# GPR.net
KiCad netlist of a schematic drawn in EAGLE
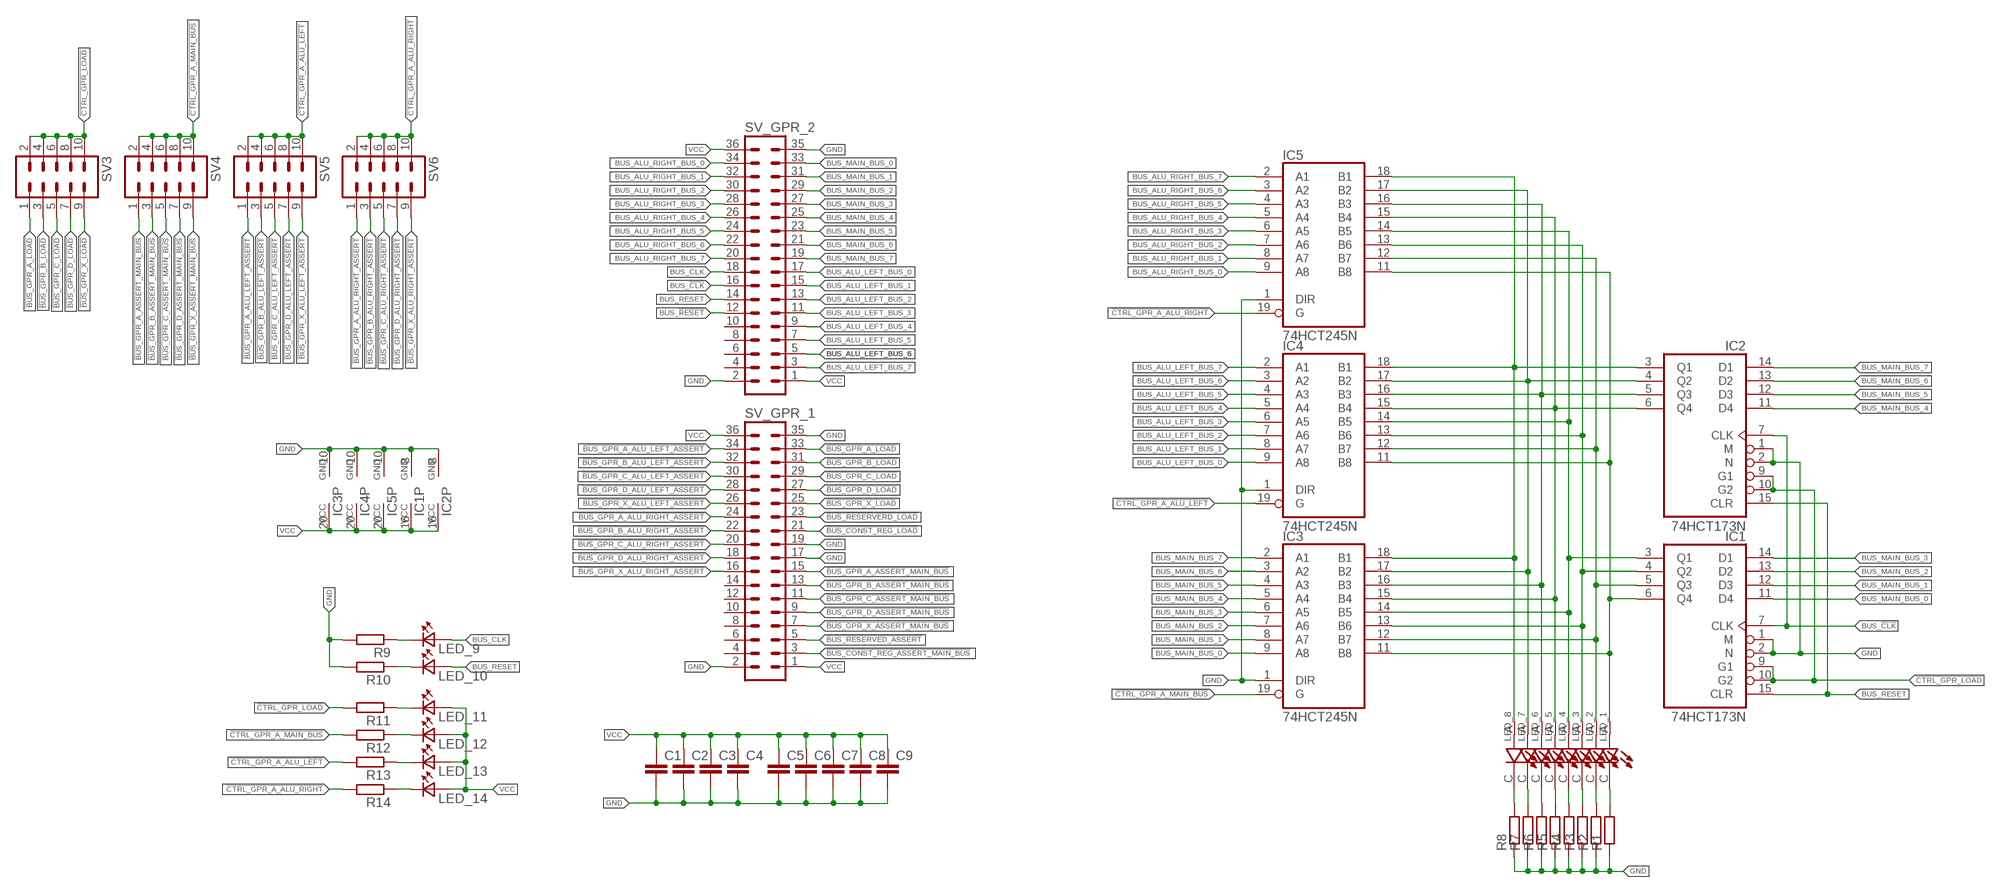
[diagram p0: schematic, sheet 1]

(export (version "E")
  (design (tool "Eeschema 10.0.6"))
  (components
    (comp (ref "C1")
      (value "C-EUC0805")
      (footprint "eagle-import:C0805")
      (libsource (lib "eagle-import") (part "C-EUC0805"))
    )
    (comp (ref "C2")
      (value "C-EUC0805")
      (footprint "eagle-import:C0805")
      (libsource (lib "eagle-import") (part "C-EUC0805"))
    )
    (comp (ref "C3")
      (value "C-EUC0805")
      (footprint "eagle-import:C0805")
      (libsource (lib "eagle-import") (part "C-EUC0805"))
    )
    (comp (ref "C4")
      (value "C-EUC0805")
      (footprint "eagle-import:C0805")
      (libsource (lib "eagle-import") (part "C-EUC0805"))
    )
    (comp (ref "C5")
      (value "C-EUC0805")
      (footprint "eagle-import:C0805")
      (libsource (lib "eagle-import") (part "C-EUC0805"))
    )
    (comp (ref "C6")
      (value "C-EUC0805")
      (footprint "eagle-import:C0805")
      (libsource (lib "eagle-import") (part "C-EUC0805"))
    )
    (comp (ref "C7")
      (value "C-EUC0805")
      (footprint "eagle-import:C0805")
      (libsource (lib "eagle-import") (part "C-EUC0805"))
    )
    (comp (ref "C8")
      (value "C-EUC0805")
      (footprint "eagle-import:C0805")
      (libsource (lib "eagle-import") (part "C-EUC0805"))
    )
    (comp (ref "C9")
      (value "C-EUC0805")
      (footprint "eagle-import:C0805")
      (libsource (lib "eagle-import") (part "C-EUC0805"))
    )
    (comp (ref "IC1")
      (value "74HCT173N")
      (footprint "eagle-import:DIL16")
      (libsource (lib "eagle-import") (part "74173NHCT"))
    )
    (comp (ref "IC2")
      (value "74HCT173N")
      (footprint "eagle-import:DIL16")
      (libsource (lib "eagle-import") (part "74173NHCT"))
    )
    (comp (ref "IC3")
      (value "74HCT245N")
      (footprint "eagle-import:DIL20")
      (libsource (lib "eagle-import") (part "74245NHCT"))
    )
    (comp (ref "IC4")
      (value "74HCT245N")
      (footprint "eagle-import:DIL20")
      (libsource (lib "eagle-import") (part "74245NHCT"))
    )
    (comp (ref "IC5")
      (value "74HCT245N")
      (footprint "eagle-import:DIL20")
      (libsource (lib "eagle-import") (part "74245NHCT"))
    )
    (comp (ref "LED_1")
      (value "LTST-C193KRKT-5A")
      (footprint "eagle-import:LEDC1608X45N")
      (fields (field (name "MANUFACTURER") "Lite-On"))
      (libsource (lib "eagle-import") (part "LTST-C193KRKT-5A"))
    )
    (comp (ref "LED_2")
      (value "LTST-C193KRKT-5A")
      (footprint "eagle-import:LEDC1608X45N")
      (fields (field (name "MANUFACTURER") "Lite-On"))
      (libsource (lib "eagle-import") (part "LTST-C193KRKT-5A"))
    )
    (comp (ref "LED_3")
      (value "LTST-C193KRKT-5A")
      (footprint "eagle-import:LEDC1608X45N")
      (fields (field (name "MANUFACTURER") "Lite-On"))
      (libsource (lib "eagle-import") (part "LTST-C193KRKT-5A"))
    )
    (comp (ref "LED_4")
      (value "LTST-C193KRKT-5A")
      (footprint "eagle-import:LEDC1608X45N")
      (fields (field (name "MANUFACTURER") "Lite-On"))
      (libsource (lib "eagle-import") (part "LTST-C193KRKT-5A"))
    )
    (comp (ref "LED_5")
      (value "LTST-C193KRKT-5A")
      (footprint "eagle-import:LEDC1608X45N")
      (fields (field (name "MANUFACTURER") "Lite-On"))
      (libsource (lib "eagle-import") (part "LTST-C193KRKT-5A"))
    )
    (comp (ref "LED_6")
      (value "LTST-C193KRKT-5A")
      (footprint "eagle-import:LEDC1608X45N")
      (fields (field (name "MANUFACTURER") "Lite-On"))
      (libsource (lib "eagle-import") (part "LTST-C193KRKT-5A"))
    )
    (comp (ref "LED_7")
      (value "LTST-C193KRKT-5A")
      (footprint "eagle-import:LEDC1608X45N")
      (fields (field (name "MANUFACTURER") "Lite-On"))
      (libsource (lib "eagle-import") (part "LTST-C193KRKT-5A"))
    )
    (comp (ref "LED_8")
      (value "LTST-C193KRKT-5A")
      (footprint "eagle-import:LEDC1608X45N")
      (fields (field (name "MANUFACTURER") "Lite-On"))
      (libsource (lib "eagle-import") (part "LTST-C193KRKT-5A"))
    )
    (comp (ref "LED_9")
      (value "LTST-C193TBKT-5A")
      (footprint "eagle-import:0603")
      (libsource (lib "eagle-import") (part "LTST-C193TBKT-5A"))
    )
    (comp (ref "LED_10")
      (value "LTST-C193TBKT-5A")
      (footprint "eagle-import:0603")
      (libsource (lib "eagle-import") (part "LTST-C193TBKT-5A"))
    )
    (comp (ref "LED_11")
      (value "LTST-C193TBKT-5A")
      (footprint "eagle-import:0603")
      (libsource (lib "eagle-import") (part "LTST-C193TBKT-5A"))
    )
    (comp (ref "LED_12")
      (value "LTST-C193TBKT-5A")
      (footprint "eagle-import:0603")
      (libsource (lib "eagle-import") (part "LTST-C193TBKT-5A"))
    )
    (comp (ref "LED_13")
      (value "LTST-C193TBKT-5A")
      (footprint "eagle-import:0603")
      (libsource (lib "eagle-import") (part "LTST-C193TBKT-5A"))
    )
    (comp (ref "LED_14")
      (value "LTST-C193TBKT-5A")
      (footprint "eagle-import:0603")
      (libsource (lib "eagle-import") (part "LTST-C193TBKT-5A"))
    )
    (comp (ref "R1")
      (value "R-EU_R0805")
      (footprint "eagle-import:R0805")
      (libsource (lib "eagle-import") (part "R-EU_R0805"))
    )
    (comp (ref "R2")
      (value "R-EU_R0805")
      (footprint "eagle-import:R0805")
      (libsource (lib "eagle-import") (part "R-EU_R0805"))
    )
    (comp (ref "R3")
      (value "R-EU_R0805")
      (footprint "eagle-import:R0805")
      (libsource (lib "eagle-import") (part "R-EU_R0805"))
    )
    (comp (ref "R4")
      (value "R-EU_R0805")
      (footprint "eagle-import:R0805")
      (libsource (lib "eagle-import") (part "R-EU_R0805"))
    )
    (comp (ref "R5")
      (value "R-EU_R0805")
      (footprint "eagle-import:R0805")
      (libsource (lib "eagle-import") (part "R-EU_R0805"))
    )
    (comp (ref "R6")
      (value "R-EU_R0805")
      (footprint "eagle-import:R0805")
      (libsource (lib "eagle-import") (part "R-EU_R0805"))
    )
    (comp (ref "R7")
      (value "R-EU_R0805")
      (footprint "eagle-import:R0805")
      (libsource (lib "eagle-import") (part "R-EU_R0805"))
    )
    (comp (ref "R8")
      (value "R-EU_R0805")
      (footprint "eagle-import:R0805")
      (libsource (lib "eagle-import") (part "R-EU_R0805"))
    )
    (comp (ref "R9")
      (value "R-EU_R0805")
      (footprint "eagle-import:R0805")
      (libsource (lib "eagle-import") (part "R-EU_R0805"))
    )
    (comp (ref "R10")
      (value "R-EU_R0805")
      (footprint "eagle-import:R0805")
      (libsource (lib "eagle-import") (part "R-EU_R0805"))
    )
    (comp (ref "R11")
      (value "R-EU_R0805")
      (footprint "eagle-import:R0805")
      (libsource (lib "eagle-import") (part "R-EU_R0805"))
    )
    (comp (ref "R12")
      (value "R-EU_R0805")
      (footprint "eagle-import:R0805")
      (libsource (lib "eagle-import") (part "R-EU_R0805"))
    )
    (comp (ref "R13")
      (value "R-EU_R0805")
      (footprint "eagle-import:R0805")
      (libsource (lib "eagle-import") (part "R-EU_R0805"))
    )
    (comp (ref "R14")
      (value "R-EU_R0805")
      (footprint "eagle-import:R0805")
      (libsource (lib "eagle-import") (part "R-EU_R0805"))
    )
    (comp (ref "SV3")
      (value "MA05-2")
      (footprint "eagle-import:MA05-2")
      (libsource (lib "eagle-import") (part "MA05-2"))
    )
    (comp (ref "SV4")
      (value "MA05-2")
      (footprint "eagle-import:MA05-2")
      (libsource (lib "eagle-import") (part "MA05-2"))
    )
    (comp (ref "SV5")
      (value "MA05-2")
      (footprint "eagle-import:MA05-2")
      (libsource (lib "eagle-import") (part "MA05-2"))
    )
    (comp (ref "SV6")
      (value "MA05-2")
      (footprint "eagle-import:MA05-2")
      (libsource (lib "eagle-import") (part "MA05-2"))
    )
    (comp (ref "SV_GPR_1")
      (value "MA18-2")
      (footprint "eagle-import:MA18-2")
      (libsource (lib "eagle-import") (part "MA18-2"))
    )
    (comp (ref "SV_GPR_2")
      (value "MA18-2")
      (footprint "eagle-import:MA18-2")
      (libsource (lib "eagle-import") (part "MA18-2"))
    )
  )
  (nets
    (net (code "1") (name "/BUS_~{CLK}") (class "Default")
      (node (ref "IC1") (pin "7") (pinfunction "CLK_7") (pintype "input"))
      (node (ref "IC2") (pin "7") (pinfunction "CLK_7") (pintype "input"))
      (node (ref "SV_GPR_2") (pin "16") (pinfunction "16_16") (pintype "passive"))
    )
    (net (code "2") (name "/BUS_~{RESET}") (class "Default")
      (node (ref "SV_GPR_2") (pin "12") (pinfunction "12_12") (pintype "passive"))
    )
    (net (code "3") (name "/~{BUS_CONST_REG_ASSERT_MAIN_BUS}") (class "Default")
      (node (ref "SV_GPR_1") (pin "3") (pinfunction "3_3") (pintype "passive"))
    )
    (net (code "4") (name "/~{BUS_CONST_REG_LOAD}") (class "Default")
      (node (ref "SV_GPR_1") (pin "21") (pinfunction "21_21") (pintype "passive"))
    )
    (net (code "5") (name "/~{BUS_GPR_A_ALU_LEFT_ASSERT}") (class "Default")
      (node (ref "SV5") (pin "1") (pinfunction "1_1") (pintype "passive"))
      (node (ref "SV_GPR_1") (pin "34") (pinfunction "34_34") (pintype "passive"))
    )
    (net (code "6") (name "/~{BUS_GPR_A_ALU_RIGHT_ASSERT}") (class "Default")
      (node (ref "SV6") (pin "1") (pinfunction "1_1") (pintype "passive"))
      (node (ref "SV_GPR_1") (pin "24") (pinfunction "24_24") (pintype "passive"))
    )
    (net (code "7") (name "/~{BUS_GPR_A_ASSERT_MAIN_BUS}") (class "Default")
      (node (ref "SV4") (pin "1") (pinfunction "1_1") (pintype "passive"))
      (node (ref "SV_GPR_1") (pin "15") (pinfunction "15_15") (pintype "passive"))
    )
    (net (code "8") (name "/~{BUS_GPR_A_LOAD}") (class "Default")
      (node (ref "SV3") (pin "1") (pinfunction "1_1") (pintype "passive"))
      (node (ref "SV_GPR_1") (pin "33") (pinfunction "33_33") (pintype "passive"))
    )
    (net (code "9") (name "/~{BUS_GPR_B_ALU_LEFT_ASSERT}") (class "Default")
      (node (ref "SV5") (pin "3") (pinfunction "3_3") (pintype "passive"))
      (node (ref "SV_GPR_1") (pin "32") (pinfunction "32_32") (pintype "passive"))
    )
    (net (code "10") (name "/~{BUS_GPR_B_ALU_RIGHT_ASSERT}") (class "Default")
      (node (ref "SV6") (pin "3") (pinfunction "3_3") (pintype "passive"))
      (node (ref "SV_GPR_1") (pin "22") (pinfunction "22_22") (pintype "passive"))
    )
    (net (code "11") (name "/~{BUS_GPR_B_ASSERT_MAIN_BUS}") (class "Default")
      (node (ref "SV4") (pin "3") (pinfunction "3_3") (pintype "passive"))
      (node (ref "SV_GPR_1") (pin "13") (pinfunction "13_13") (pintype "passive"))
    )
    (net (code "12") (name "/~{BUS_GPR_B_LOAD}") (class "Default")
      (node (ref "SV3") (pin "3") (pinfunction "3_3") (pintype "passive"))
      (node (ref "SV_GPR_1") (pin "31") (pinfunction "31_31") (pintype "passive"))
    )
    (net (code "13") (name "/~{BUS_GPR_C_ALU_LEFT_ASSERT}") (class "Default")
      (node (ref "SV5") (pin "5") (pinfunction "5_5") (pintype "passive"))
      (node (ref "SV_GPR_1") (pin "30") (pinfunction "30_30") (pintype "passive"))
    )
    (net (code "14") (name "/~{BUS_GPR_C_ALU_RIGHT_ASSERT}") (class "Default")
      (node (ref "SV6") (pin "5") (pinfunction "5_5") (pintype "passive"))
      (node (ref "SV_GPR_1") (pin "20") (pinfunction "20_20") (pintype "passive"))
    )
    (net (code "15") (name "/~{BUS_GPR_C_ASSERT_MAIN_BUS}") (class "Default")
      (node (ref "SV4") (pin "5") (pinfunction "5_5") (pintype "passive"))
      (node (ref "SV_GPR_1") (pin "11") (pinfunction "11_11") (pintype "passive"))
    )
    (net (code "16") (name "/~{BUS_GPR_C_LOAD}") (class "Default")
      (node (ref "SV3") (pin "5") (pinfunction "5_5") (pintype "passive"))
      (node (ref "SV_GPR_1") (pin "29") (pinfunction "29_29") (pintype "passive"))
    )
    (net (code "17") (name "/~{BUS_GPR_D_ALU_LEFT_ASSERT}") (class "Default")
      (node (ref "SV5") (pin "7") (pinfunction "7_7") (pintype "passive"))
      (node (ref "SV_GPR_1") (pin "28") (pinfunction "28_28") (pintype "passive"))
    )
    (net (code "18") (name "/~{BUS_GPR_D_ALU_RIGHT_ASSERT}") (class "Default")
      (node (ref "SV6") (pin "7") (pinfunction "7_7") (pintype "passive"))
      (node (ref "SV_GPR_1") (pin "18") (pinfunction "18_18") (pintype "passive"))
    )
    (net (code "19") (name "/~{BUS_GPR_D_ASSERT_MAIN_BUS}") (class "Default")
      (node (ref "SV4") (pin "7") (pinfunction "7_7") (pintype "passive"))
      (node (ref "SV_GPR_1") (pin "9") (pinfunction "9_9") (pintype "passive"))
    )
    (net (code "20") (name "/~{BUS_GPR_D_LOAD}") (class "Default")
      (node (ref "SV3") (pin "7") (pinfunction "7_7") (pintype "passive"))
      (node (ref "SV_GPR_1") (pin "27") (pinfunction "27_27") (pintype "passive"))
    )
    (net (code "21") (name "/~{BUS_GPR_X_ALU_LEFT_ASSERT}") (class "Default")
      (node (ref "SV5") (pin "9") (pinfunction "9_9") (pintype "passive"))
      (node (ref "SV_GPR_1") (pin "26") (pinfunction "26_26") (pintype "passive"))
    )
    (net (code "22") (name "/~{BUS_GPR_X_ALU_RIGHT_ASSERT}") (class "Default")
      (node (ref "SV6") (pin "9") (pinfunction "9_9") (pintype "passive"))
      (node (ref "SV_GPR_1") (pin "16") (pinfunction "16_16") (pintype "passive"))
    )
    (net (code "23") (name "/~{BUS_GPR_X_ASSERT_MAIN_BUS}") (class "Default")
      (node (ref "SV4") (pin "9") (pinfunction "9_9") (pintype "passive"))
      (node (ref "SV_GPR_1") (pin "7") (pinfunction "7_7") (pintype "passive"))
    )
    (net (code "24") (name "/~{BUS_GPR_X_LOAD}") (class "Default")
      (node (ref "SV3") (pin "9") (pinfunction "9_9") (pintype "passive"))
      (node (ref "SV_GPR_1") (pin "25") (pinfunction "25_25") (pintype "passive"))
    )
    (net (code "25") (name "/~{BUS_RESERVED_ASSERT}") (class "Default")
      (node (ref "SV_GPR_1") (pin "5") (pinfunction "5_5") (pintype "passive"))
    )
    (net (code "26") (name "/~{BUS_RESERVERD_LOAD}") (class "Default")
      (node (ref "SV_GPR_1") (pin "23") (pinfunction "23_23") (pintype "passive"))
    )
    (net (code "27") (name "/~{CTRL_GPR_A_ALU_LEFT}") (class "Default")
      (node (ref "IC4") (pin "19") (pinfunction "G_19") (pintype "input"))
      (node (ref "R13") (pin "2") (pinfunction "2_2") (pintype "passive"))
      (node (ref "SV5") (pin "10") (pinfunction "10_10") (pintype "passive"))
      (node (ref "SV5") (pin "2") (pinfunction "2_2") (pintype "passive"))
      (node (ref "SV5") (pin "4") (pinfunction "4_4") (pintype "passive"))
      (node (ref "SV5") (pin "6") (pinfunction "6_6") (pintype "passive"))
      (node (ref "SV5") (pin "8") (pinfunction "8_8") (pintype "passive"))
    )
    (net (code "28") (name "/~{CTRL_GPR_A_ALU_RIGHT}") (class "Default")
      (node (ref "IC5") (pin "19") (pinfunction "G_19") (pintype "input"))
      (node (ref "R14") (pin "2") (pinfunction "2_2") (pintype "passive"))
      (node (ref "SV6") (pin "10") (pinfunction "10_10") (pintype "passive"))
      (node (ref "SV6") (pin "2") (pinfunction "2_2") (pintype "passive"))
      (node (ref "SV6") (pin "4") (pinfunction "4_4") (pintype "passive"))
      (node (ref "SV6") (pin "6") (pinfunction "6_6") (pintype "passive"))
      (node (ref "SV6") (pin "8") (pinfunction "8_8") (pintype "passive"))
    )
    (net (code "29") (name "/~{CTRL_GPR_A_MAIN_BUS}") (class "Default")
      (node (ref "IC3") (pin "19") (pinfunction "G_19") (pintype "input"))
      (node (ref "R12") (pin "2") (pinfunction "2_2") (pintype "passive"))
      (node (ref "SV4") (pin "10") (pinfunction "10_10") (pintype "passive"))
      (node (ref "SV4") (pin "2") (pinfunction "2_2") (pintype "passive"))
      (node (ref "SV4") (pin "4") (pinfunction "4_4") (pintype "passive"))
      (node (ref "SV4") (pin "6") (pinfunction "6_6") (pintype "passive"))
      (node (ref "SV4") (pin "8") (pinfunction "8_8") (pintype "passive"))
    )
    (net (code "30") (name "/~{CTRL_GPR_LOAD}") (class "Default")
      (node (ref "IC1") (pin "10") (pinfunction "G2_10") (pintype "input"))
      (node (ref "IC1") (pin "9") (pinfunction "G1_9") (pintype "input"))
      (node (ref "IC2") (pin "10") (pinfunction "G2_10") (pintype "input"))
      (node (ref "IC2") (pin "9") (pinfunction "G1_9") (pintype "input"))
      (node (ref "R11") (pin "2") (pinfunction "2_2") (pintype "passive"))
      (node (ref "SV3") (pin "10") (pinfunction "10_10") (pintype "passive"))
      (node (ref "SV3") (pin "2") (pinfunction "2_2") (pintype "passive"))
      (node (ref "SV3") (pin "4") (pinfunction "4_4") (pintype "passive"))
      (node (ref "SV3") (pin "6") (pinfunction "6_6") (pintype "passive"))
      (node (ref "SV3") (pin "8") (pinfunction "8_8") (pintype "passive"))
    )
    (net (code "31") (name "BUS_ALU_LEFT_BUS_0") (class "Default")
      (node (ref "IC4") (pin "9") (pinfunction "A8_9") (pintype "bidirectional"))
      (node (ref "SV_GPR_2") (pin "17") (pinfunction "17_17") (pintype "passive"))
    )
    (net (code "32") (name "BUS_ALU_LEFT_BUS_1") (class "Default")
      (node (ref "IC4") (pin "8") (pinfunction "A7_8") (pintype "bidirectional"))
      (node (ref "SV_GPR_2") (pin "15") (pinfunction "15_15") (pintype "passive"))
    )
    (net (code "33") (name "BUS_ALU_LEFT_BUS_2") (class "Default")
      (node (ref "IC4") (pin "7") (pinfunction "A6_7") (pintype "bidirectional"))
      (node (ref "SV_GPR_2") (pin "13") (pinfunction "13_13") (pintype "passive"))
    )
    (net (code "34") (name "BUS_ALU_LEFT_BUS_3") (class "Default")
      (node (ref "IC4") (pin "6") (pinfunction "A5_6") (pintype "bidirectional"))
      (node (ref "SV_GPR_2") (pin "11") (pinfunction "11_11") (pintype "passive"))
    )
    (net (code "35") (name "BUS_ALU_LEFT_BUS_4") (class "Default")
      (node (ref "IC4") (pin "5") (pinfunction "A4_5") (pintype "bidirectional"))
      (node (ref "SV_GPR_2") (pin "9") (pinfunction "9_9") (pintype "passive"))
    )
    (net (code "36") (name "BUS_ALU_LEFT_BUS_5") (class "Default")
      (node (ref "IC4") (pin "4") (pinfunction "A3_4") (pintype "bidirectional"))
      (node (ref "SV_GPR_2") (pin "7") (pinfunction "7_7") (pintype "passive"))
    )
    (net (code "37") (name "BUS_ALU_LEFT_BUS_6") (class "Default")
      (node (ref "IC4") (pin "3") (pinfunction "A2_3") (pintype "bidirectional"))
      (node (ref "SV_GPR_2") (pin "5") (pinfunction "5_5") (pintype "passive"))
    )
    (net (code "38") (name "BUS_ALU_LEFT_BUS_7") (class "Default")
      (node (ref "IC4") (pin "2") (pinfunction "A1_2") (pintype "bidirectional"))
      (node (ref "SV_GPR_2") (pin "3") (pinfunction "3_3") (pintype "passive"))
    )
    (net (code "39") (name "BUS_ALU_RIGHT_BUS_0") (class "Default")
      (node (ref "IC5") (pin "9") (pinfunction "A8_9") (pintype "bidirectional"))
      (node (ref "SV_GPR_2") (pin "34") (pinfunction "34_34") (pintype "passive"))
    )
    (net (code "40") (name "BUS_ALU_RIGHT_BUS_1") (class "Default")
      (node (ref "IC5") (pin "8") (pinfunction "A7_8") (pintype "bidirectional"))
      (node (ref "SV_GPR_2") (pin "32") (pinfunction "32_32") (pintype "passive"))
    )
    (net (code "41") (name "BUS_ALU_RIGHT_BUS_2") (class "Default")
      (node (ref "IC5") (pin "7") (pinfunction "A6_7") (pintype "bidirectional"))
      (node (ref "SV_GPR_2") (pin "30") (pinfunction "30_30") (pintype "passive"))
    )
    (net (code "42") (name "BUS_ALU_RIGHT_BUS_3") (class "Default")
      (node (ref "IC5") (pin "6") (pinfunction "A5_6") (pintype "bidirectional"))
      (node (ref "SV_GPR_2") (pin "28") (pinfunction "28_28") (pintype "passive"))
    )
    (net (code "43") (name "BUS_ALU_RIGHT_BUS_4") (class "Default")
      (node (ref "IC5") (pin "5") (pinfunction "A4_5") (pintype "bidirectional"))
      (node (ref "SV_GPR_2") (pin "26") (pinfunction "26_26") (pintype "passive"))
    )
    (net (code "44") (name "BUS_ALU_RIGHT_BUS_5") (class "Default")
      (node (ref "IC5") (pin "4") (pinfunction "A3_4") (pintype "bidirectional"))
      (node (ref "SV_GPR_2") (pin "24") (pinfunction "24_24") (pintype "passive"))
    )
    (net (code "45") (name "BUS_ALU_RIGHT_BUS_6") (class "Default")
      (node (ref "IC5") (pin "3") (pinfunction "A2_3") (pintype "bidirectional"))
      (node (ref "SV_GPR_2") (pin "22") (pinfunction "22_22") (pintype "passive"))
    )
    (net (code "46") (name "BUS_ALU_RIGHT_BUS_7") (class "Default")
      (node (ref "IC5") (pin "2") (pinfunction "A1_2") (pintype "bidirectional"))
      (node (ref "SV_GPR_2") (pin "20") (pinfunction "20_20") (pintype "passive"))
    )
    (net (code "47") (name "BUS_CLK") (class "Default")
      (node (ref "LED_9") (pin "2") (pinfunction "A2_2") (pintype "passive"))
      (node (ref "SV_GPR_2") (pin "18") (pinfunction "18_18") (pintype "passive"))
    )
    (net (code "48") (name "BUS_MAIN_BUS_0") (class "Default")
      (node (ref "IC1") (pin "11") (pinfunction "D4_11") (pintype "input"))
      (node (ref "IC3") (pin "9") (pinfunction "A8_9") (pintype "bidirectional"))
      (node (ref "SV_GPR_2") (pin "33") (pinfunction "33_33") (pintype "passive"))
    )
    (net (code "49") (name "BUS_MAIN_BUS_1") (class "Default")
      (node (ref "IC1") (pin "12") (pinfunction "D3_12") (pintype "input"))
      (node (ref "IC3") (pin "8") (pinfunction "A7_8") (pintype "bidirectional"))
      (node (ref "SV_GPR_2") (pin "31") (pinfunction "31_31") (pintype "passive"))
    )
    (net (code "50") (name "BUS_MAIN_BUS_2") (class "Default")
      (node (ref "IC1") (pin "13") (pinfunction "D2_13") (pintype "input"))
      (node (ref "IC3") (pin "7") (pinfunction "A6_7") (pintype "bidirectional"))
      (node (ref "SV_GPR_2") (pin "29") (pinfunction "29_29") (pintype "passive"))
    )
    (net (code "51") (name "BUS_MAIN_BUS_3") (class "Default")
      (node (ref "IC1") (pin "14") (pinfunction "D1_14") (pintype "input"))
      (node (ref "IC3") (pin "6") (pinfunction "A5_6") (pintype "bidirectional"))
      (node (ref "SV_GPR_2") (pin "27") (pinfunction "27_27") (pintype "passive"))
    )
    (net (code "52") (name "BUS_MAIN_BUS_4") (class "Default")
      (node (ref "IC2") (pin "11") (pinfunction "D4_11") (pintype "input"))
      (node (ref "IC3") (pin "5") (pinfunction "A4_5") (pintype "bidirectional"))
      (node (ref "SV_GPR_2") (pin "25") (pinfunction "25_25") (pintype "passive"))
    )
    (net (code "53") (name "BUS_MAIN_BUS_5") (class "Default")
      (node (ref "IC2") (pin "12") (pinfunction "D3_12") (pintype "input"))
      (node (ref "IC3") (pin "4") (pinfunction "A3_4") (pintype "bidirectional"))
      (node (ref "SV_GPR_2") (pin "23") (pinfunction "23_23") (pintype "passive"))
    )
    (net (code "54") (name "BUS_MAIN_BUS_6") (class "Default")
      (node (ref "IC2") (pin "13") (pinfunction "D2_13") (pintype "input"))
      (node (ref "IC3") (pin "3") (pinfunction "A2_3") (pintype "bidirectional"))
      (node (ref "SV_GPR_2") (pin "21") (pinfunction "21_21") (pintype "passive"))
    )
    (net (code "55") (name "BUS_MAIN_BUS_7") (class "Default")
      (node (ref "IC2") (pin "14") (pinfunction "D1_14") (pintype "input"))
      (node (ref "IC3") (pin "2") (pinfunction "A1_2") (pintype "bidirectional"))
      (node (ref "SV_GPR_2") (pin "19") (pinfunction "19_19") (pintype "passive"))
    )
    (net (code "56") (name "BUS_RESET") (class "Default")
      (node (ref "IC1") (pin "15") (pinfunction "CLR_15") (pintype "input"))
      (node (ref "IC2") (pin "15") (pinfunction "CLR_15") (pintype "input"))
      (node (ref "LED_10") (pin "2") (pinfunction "A2_2") (pintype "passive"))
      (node (ref "SV_GPR_2") (pin "14") (pinfunction "14_14") (pintype "passive"))
    )
    (net (code "57") (name "GND") (class "Default")
      (node (ref "C1") (pin "2") (pinfunction "2_2") (pintype "passive"))
      (node (ref "C2") (pin "2") (pinfunction "2_2") (pintype "passive"))
      (node (ref "C3") (pin "2") (pinfunction "2_2") (pintype "passive"))
      (node (ref "C4") (pin "2") (pinfunction "2_2") (pintype "passive"))
      (node (ref "C5") (pin "2") (pinfunction "2_2") (pintype "passive"))
      (node (ref "C6") (pin "2") (pinfunction "2_2") (pintype "passive"))
      (node (ref "C7") (pin "2") (pinfunction "2_2") (pintype "passive"))
      (node (ref "C8") (pin "2") (pinfunction "2_2") (pintype "passive"))
      (node (ref "C9") (pin "2") (pinfunction "2_2") (pintype "passive"))
      (node (ref "IC1") (pin "1") (pinfunction "M_1") (pintype "input"))
      (node (ref "IC1") (pin "2") (pinfunction "N_2") (pintype "input"))
      (node (ref "IC1") (pin "8") (pinfunction "GND_8") (pintype "power_in"))
      (node (ref "IC2") (pin "1") (pinfunction "M_1") (pintype "input"))
      (node (ref "IC2") (pin "2") (pinfunction "N_2") (pintype "input"))
      (node (ref "IC2") (pin "8") (pinfunction "GND_8") (pintype "power_in"))
      (node (ref "IC3") (pin "1") (pinfunction "DIR_1") (pintype "input"))
      (node (ref "IC3") (pin "10") (pinfunction "GND_10") (pintype "power_in"))
      (node (ref "IC4") (pin "1") (pinfunction "DIR_1") (pintype "input"))
      (node (ref "IC4") (pin "10") (pinfunction "GND_10") (pintype "power_in"))
      (node (ref "IC5") (pin "1") (pinfunction "DIR_1") (pintype "input"))
      (node (ref "IC5") (pin "10") (pinfunction "GND_10") (pintype "power_in"))
      (node (ref "R1") (pin "1") (pinfunction "1_1") (pintype "passive"))
      (node (ref "R10") (pin "2") (pinfunction "2_2") (pintype "passive"))
      (node (ref "R2") (pin "1") (pinfunction "1_1") (pintype "passive"))
      (node (ref "R3") (pin "1") (pinfunction "1_1") (pintype "passive"))
      (node (ref "R4") (pin "1") (pinfunction "1_1") (pintype "passive"))
      (node (ref "R5") (pin "1") (pinfunction "1_1") (pintype "passive"))
      (node (ref "R6") (pin "1") (pinfunction "1_1") (pintype "passive"))
      (node (ref "R7") (pin "1") (pinfunction "1_1") (pintype "passive"))
      (node (ref "R8") (pin "1") (pinfunction "1_1") (pintype "passive"))
      (node (ref "R9") (pin "2") (pinfunction "2_2") (pintype "passive"))
      (node (ref "SV_GPR_1") (pin "17") (pinfunction "17_17") (pintype "passive"))
      (node (ref "SV_GPR_1") (pin "19") (pinfunction "19_19") (pintype "passive"))
      (node (ref "SV_GPR_1") (pin "2") (pinfunction "2_2") (pintype "passive"))
      (node (ref "SV_GPR_1") (pin "35") (pinfunction "35_35") (pintype "passive"))
      (node (ref "SV_GPR_2") (pin "2") (pinfunction "2_2") (pintype "passive"))
      (node (ref "SV_GPR_2") (pin "35") (pinfunction "35_35") (pintype "passive"))
    )
    (net (code "58") (name "Net-(IC1A-Q1)") (class "Default")
      (node (ref "IC1") (pin "3") (pinfunction "Q1_3") (pintype "tri_state"))
      (node (ref "IC3") (pin "14") (pinfunction "B5_14") (pintype "bidirectional"))
      (node (ref "IC4") (pin "14") (pinfunction "B5_14") (pintype "bidirectional"))
      (node (ref "IC5") (pin "14") (pinfunction "B5_14") (pintype "bidirectional"))
      (node (ref "LED_4") (pin "A") (pinfunction "A_A") (pintype "passive"))
    )
    (net (code "59") (name "Net-(IC1A-Q2)") (class "Default")
      (node (ref "IC1") (pin "4") (pinfunction "Q2_4") (pintype "tri_state"))
      (node (ref "IC3") (pin "13") (pinfunction "B6_13") (pintype "bidirectional"))
      (node (ref "IC4") (pin "13") (pinfunction "B6_13") (pintype "bidirectional"))
      (node (ref "IC5") (pin "13") (pinfunction "B6_13") (pintype "bidirectional"))
      (node (ref "LED_3") (pin "A") (pinfunction "A_A") (pintype "passive"))
    )
    (net (code "60") (name "Net-(IC1A-Q3)") (class "Default")
      (node (ref "IC1") (pin "5") (pinfunction "Q3_5") (pintype "tri_state"))
      (node (ref "IC3") (pin "12") (pinfunction "B7_12") (pintype "bidirectional"))
      (node (ref "IC4") (pin "12") (pinfunction "B7_12") (pintype "bidirectional"))
      (node (ref "IC5") (pin "12") (pinfunction "B7_12") (pintype "bidirectional"))
      (node (ref "LED_2") (pin "A") (pinfunction "A_A") (pintype "passive"))
    )
    (net (code "61") (name "Net-(IC1A-Q4)") (class "Default")
      (node (ref "IC1") (pin "6") (pinfunction "Q4_6") (pintype "tri_state"))
      (node (ref "IC3") (pin "11") (pinfunction "B8_11") (pintype "bidirectional"))
      (node (ref "IC4") (pin "11") (pinfunction "B8_11") (pintype "bidirectional"))
      (node (ref "IC5") (pin "11") (pinfunction "B8_11") (pintype "bidirectional"))
      (node (ref "LED_1") (pin "A") (pinfunction "A_A") (pintype "passive"))
    )
    (net (code "62") (name "Net-(IC2A-Q1)") (class "Default")
      (node (ref "IC2") (pin "3") (pinfunction "Q1_3") (pintype "tri_state"))
      (node (ref "IC3") (pin "18") (pinfunction "B1_18") (pintype "bidirectional"))
      (node (ref "IC4") (pin "18") (pinfunction "B1_18") (pintype "bidirectional"))
      (node (ref "IC5") (pin "18") (pinfunction "B1_18") (pintype "bidirectional"))
      (node (ref "LED_8") (pin "A") (pinfunction "A_A") (pintype "passive"))
    )
    (net (code "63") (name "Net-(IC2A-Q2)") (class "Default")
      (node (ref "IC2") (pin "4") (pinfunction "Q2_4") (pintype "tri_state"))
      (node (ref "IC3") (pin "17") (pinfunction "B2_17") (pintype "bidirectional"))
      (node (ref "IC4") (pin "17") (pinfunction "B2_17") (pintype "bidirectional"))
      (node (ref "IC5") (pin "17") (pinfunction "B2_17") (pintype "bidirectional"))
      (node (ref "LED_7") (pin "A") (pinfunction "A_A") (pintype "passive"))
    )
    (net (code "64") (name "Net-(IC2A-Q3)") (class "Default")
      (node (ref "IC2") (pin "5") (pinfunction "Q3_5") (pintype "tri_state"))
      (node (ref "IC3") (pin "16") (pinfunction "B3_16") (pintype "bidirectional"))
      (node (ref "IC4") (pin "16") (pinfunction "B3_16") (pintype "bidirectional"))
      (node (ref "IC5") (pin "16") (pinfunction "B3_16") (pintype "bidirectional"))
      (node (ref "LED_6") (pin "A") (pinfunction "A_A") (pintype "passive"))
    )
    (net (code "65") (name "Net-(IC2A-Q4)") (class "Default")
      (node (ref "IC2") (pin "6") (pinfunction "Q4_6") (pintype "tri_state"))
      (node (ref "IC3") (pin "15") (pinfunction "B4_15") (pintype "bidirectional"))
      (node (ref "IC4") (pin "15") (pinfunction "B4_15") (pintype "bidirectional"))
      (node (ref "IC5") (pin "15") (pinfunction "B4_15") (pintype "bidirectional"))
      (node (ref "LED_5") (pin "A") (pinfunction "A_A") (pintype "passive"))
    )
    (net (code "66") (name "Net-(LED_1-PadC)") (class "Default")
      (node (ref "LED_1") (pin "C") (pinfunction "C_C") (pintype "passive"))
      (node (ref "R1") (pin "2") (pinfunction "2_2") (pintype "passive"))
    )
    (net (code "67") (name "Net-(LED_2-PadC)") (class "Default")
      (node (ref "LED_2") (pin "C") (pinfunction "C_C") (pintype "passive"))
      (node (ref "R2") (pin "2") (pinfunction "2_2") (pintype "passive"))
    )
    (net (code "68") (name "Net-(LED_3-PadC)") (class "Default")
      (node (ref "LED_3") (pin "C") (pinfunction "C_C") (pintype "passive"))
      (node (ref "R3") (pin "2") (pinfunction "2_2") (pintype "passive"))
    )
    (net (code "69") (name "Net-(LED_4-PadC)") (class "Default")
      (node (ref "LED_4") (pin "C") (pinfunction "C_C") (pintype "passive"))
      (node (ref "R4") (pin "2") (pinfunction "2_2") (pintype "passive"))
    )
    (net (code "70") (name "Net-(LED_5-PadC)") (class "Default")
      (node (ref "LED_5") (pin "C") (pinfunction "C_C") (pintype "passive"))
      (node (ref "R5") (pin "2") (pinfunction "2_2") (pintype "passive"))
    )
    (net (code "71") (name "Net-(LED_6-PadC)") (class "Default")
      (node (ref "LED_6") (pin "C") (pinfunction "C_C") (pintype "passive"))
      (node (ref "R6") (pin "2") (pinfunction "2_2") (pintype "passive"))
    )
    (net (code "72") (name "Net-(LED_7-PadC)") (class "Default")
      (node (ref "LED_7") (pin "C") (pinfunction "C_C") (pintype "passive"))
      (node (ref "R7") (pin "2") (pinfunction "2_2") (pintype "passive"))
    )
    (net (code "73") (name "Net-(LED_8-PadC)") (class "Default")
      (node (ref "LED_8") (pin "C") (pinfunction "C_C") (pintype "passive"))
      (node (ref "R8") (pin "2") (pinfunction "2_2") (pintype "passive"))
    )
    (net (code "74") (name "Net-(LED_9-K2)") (class "Default")
      (node (ref "LED_9") (pin "1") (pinfunction "K2_1") (pintype "passive"))
      (node (ref "R9") (pin "1") (pinfunction "1_1") (pintype "passive"))
    )
    (net (code "75") (name "Net-(LED_10-K2)") (class "Default")
      (node (ref "LED_10") (pin "1") (pinfunction "K2_1") (pintype "passive"))
      (node (ref "R10") (pin "1") (pinfunction "1_1") (pintype "passive"))
    )
    (net (code "76") (name "Net-(LED_11-K2)") (class "Default")
      (node (ref "LED_11") (pin "1") (pinfunction "K2_1") (pintype "passive"))
      (node (ref "R11") (pin "1") (pinfunction "1_1") (pintype "passive"))
    )
    (net (code "77") (name "Net-(LED_12-K2)") (class "Default")
      (node (ref "LED_12") (pin "1") (pinfunction "K2_1") (pintype "passive"))
      (node (ref "R12") (pin "1") (pinfunction "1_1") (pintype "passive"))
    )
    (net (code "78") (name "Net-(LED_13-K2)") (class "Default")
      (node (ref "LED_13") (pin "1") (pinfunction "K2_1") (pintype "passive"))
      (node (ref "R13") (pin "1") (pinfunction "1_1") (pintype "passive"))
    )
    (net (code "79") (name "Net-(LED_14-K2)") (class "Default")
      (node (ref "LED_14") (pin "1") (pinfunction "K2_1") (pintype "passive"))
      (node (ref "R14") (pin "1") (pinfunction "1_1") (pintype "passive"))
    )
    (net (code "80") (name "VCC") (class "Default")
      (node (ref "C1") (pin "1") (pinfunction "1_1") (pintype "passive"))
      (node (ref "C2") (pin "1") (pinfunction "1_1") (pintype "passive"))
      (node (ref "C3") (pin "1") (pinfunction "1_1") (pintype "passive"))
      (node (ref "C4") (pin "1") (pinfunction "1_1") (pintype "passive"))
      (node (ref "C5") (pin "1") (pinfunction "1_1") (pintype "passive"))
      (node (ref "C6") (pin "1") (pinfunction "1_1") (pintype "passive"))
      (node (ref "C7") (pin "1") (pinfunction "1_1") (pintype "passive"))
      (node (ref "C8") (pin "1") (pinfunction "1_1") (pintype "passive"))
      (node (ref "C9") (pin "1") (pinfunction "1_1") (pintype "passive"))
      (node (ref "IC1") (pin "16") (pinfunction "VCC_16") (pintype "power_in"))
      (node (ref "IC2") (pin "16") (pinfunction "VCC_16") (pintype "power_in"))
      (node (ref "IC3") (pin "20") (pinfunction "VCC_20") (pintype "power_in"))
      (node (ref "IC4") (pin "20") (pinfunction "VCC_20") (pintype "power_in"))
      (node (ref "IC5") (pin "20") (pinfunction "VCC_20") (pintype "power_in"))
      (node (ref "LED_11") (pin "2") (pinfunction "A2_2") (pintype "passive"))
      (node (ref "LED_12") (pin "2") (pinfunction "A2_2") (pintype "passive"))
      (node (ref "LED_13") (pin "2") (pinfunction "A2_2") (pintype "passive"))
      (node (ref "LED_14") (pin "2") (pinfunction "A2_2") (pintype "passive"))
      (node (ref "SV_GPR_1") (pin "1") (pinfunction "1_1") (pintype "passive"))
      (node (ref "SV_GPR_1") (pin "36") (pinfunction "36_36") (pintype "passive"))
      (node (ref "SV_GPR_2") (pin "1") (pinfunction "1_1") (pintype "passive"))
      (node (ref "SV_GPR_2") (pin "36") (pinfunction "36_36") (pintype "passive"))
    )
    (net (code "81") (name "unconnected-(SV_GPR_1-Pad4)") (class "Default")
      (node (ref "SV_GPR_1") (pin "4") (pinfunction "4_4") (pintype "passive"))
    )
    (net (code "82") (name "unconnected-(SV_GPR_1-Pad6)") (class "Default")
      (node (ref "SV_GPR_1") (pin "6") (pinfunction "6_6") (pintype "passive"))
    )
    (net (code "83") (name "unconnected-(SV_GPR_1-Pad8)") (class "Default")
      (node (ref "SV_GPR_1") (pin "8") (pinfunction "8_8") (pintype "passive"))
    )
    (net (code "84") (name "unconnected-(SV_GPR_1-Pad10)") (class "Default")
      (node (ref "SV_GPR_1") (pin "10") (pinfunction "10_10") (pintype "passive"))
    )
    (net (code "85") (name "unconnected-(SV_GPR_1-Pad12)") (class "Default")
      (node (ref "SV_GPR_1") (pin "12") (pinfunction "12_12") (pintype "passive"))
    )
    (net (code "86") (name "unconnected-(SV_GPR_1-Pad14)") (class "Default")
      (node (ref "SV_GPR_1") (pin "14") (pinfunction "14_14") (pintype "passive"))
    )
    (net (code "87") (name "unconnected-(SV_GPR_2-Pad4)") (class "Default")
      (node (ref "SV_GPR_2") (pin "4") (pinfunction "4_4") (pintype "passive"))
    )
    (net (code "88") (name "unconnected-(SV_GPR_2-Pad6)") (class "Default")
      (node (ref "SV_GPR_2") (pin "6") (pinfunction "6_6") (pintype "passive"))
    )
    (net (code "89") (name "unconnected-(SV_GPR_2-Pad8)") (class "Default")
      (node (ref "SV_GPR_2") (pin "8") (pinfunction "8_8") (pintype "passive"))
    )
    (net (code "90") (name "unconnected-(SV_GPR_2-Pad10)") (class "Default")
      (node (ref "SV_GPR_2") (pin "10") (pinfunction "10_10") (pintype "passive"))
    )
  )
)
